# 20190105_ORIGAMI_V1-1-V-FIXED.net
KiCad netlist of a schematic drawn in EAGLE
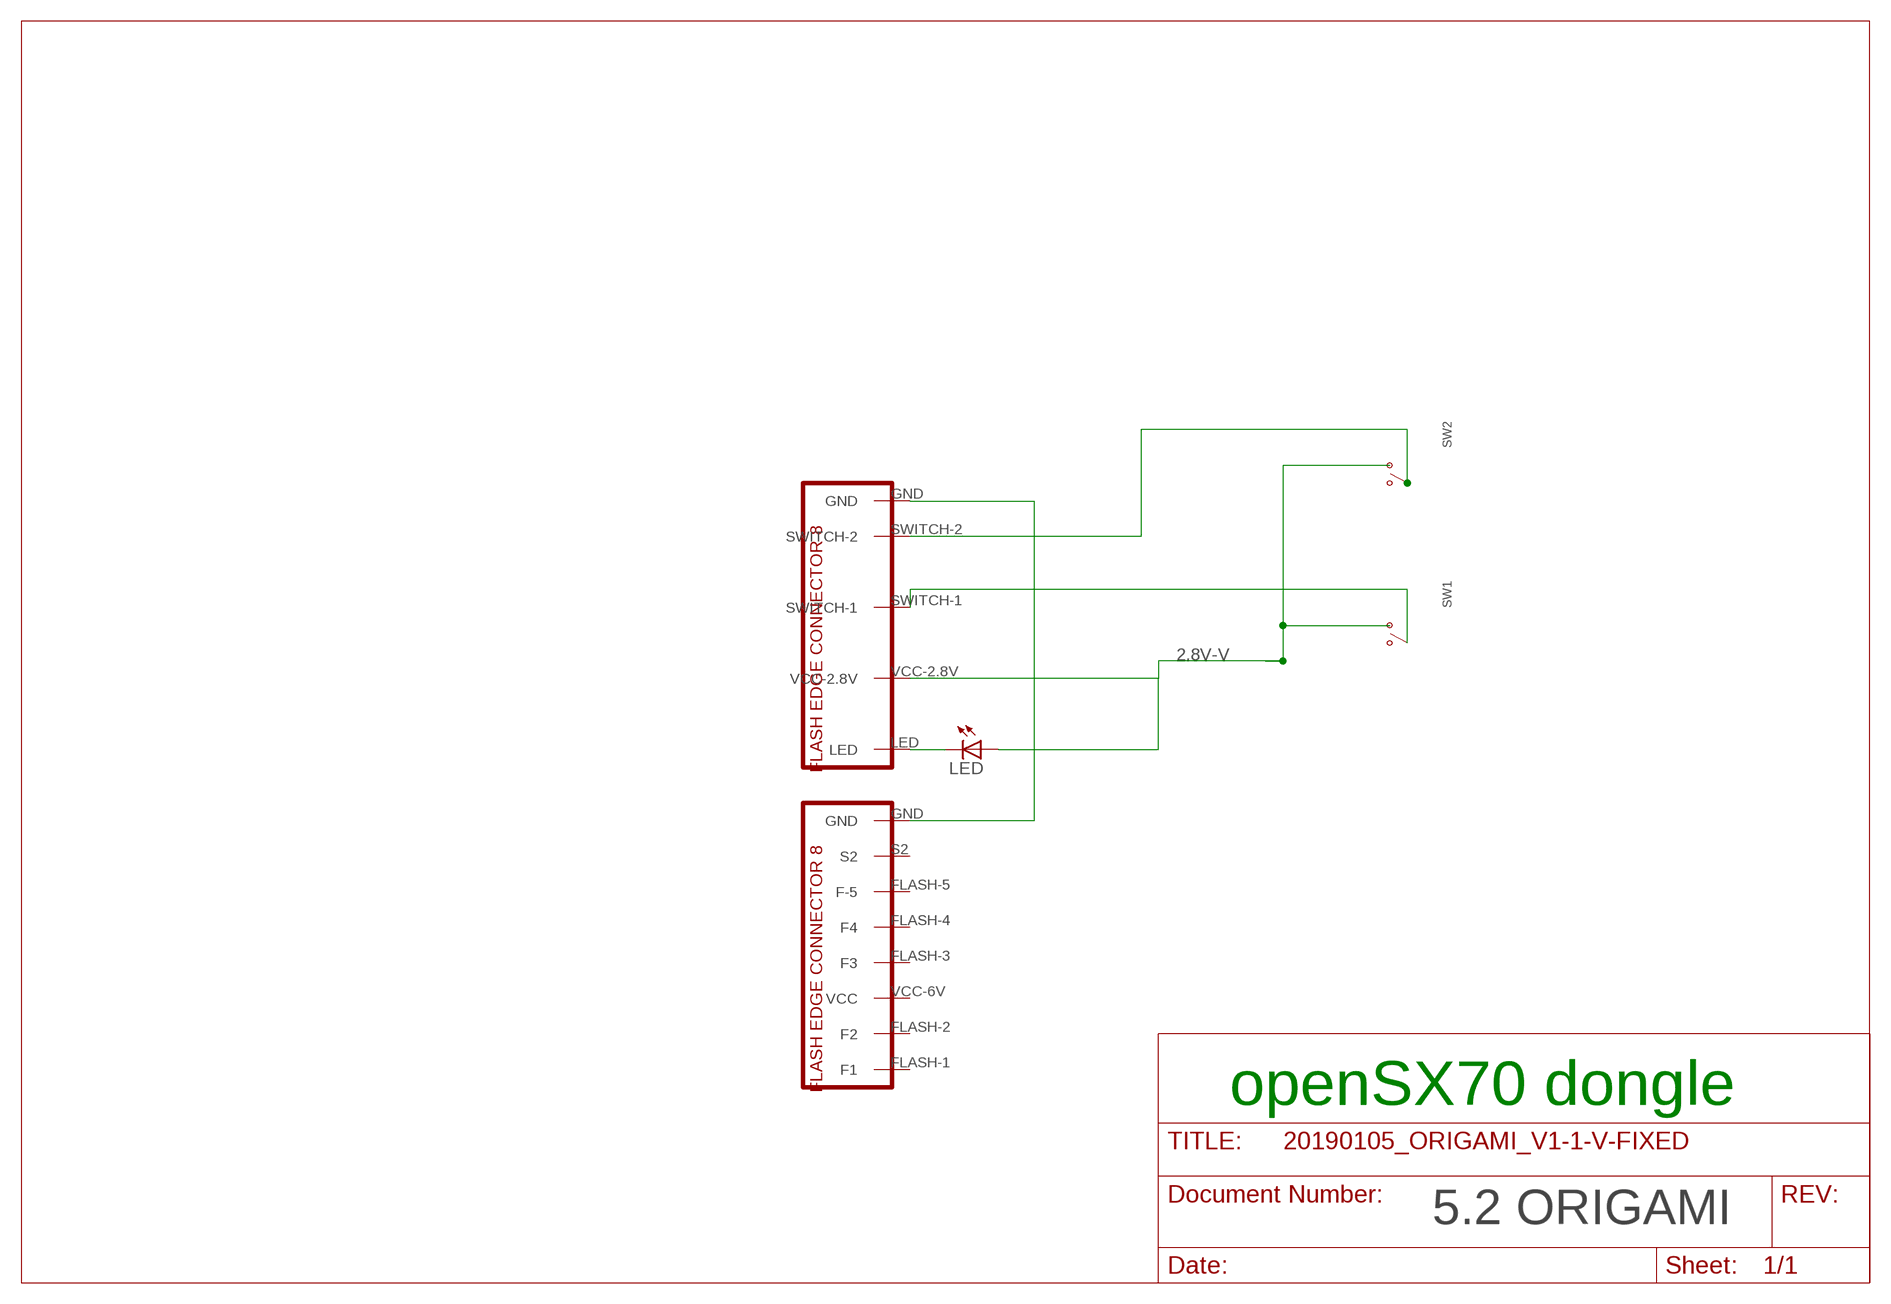
[diagram p0: schematic, sheet 1]

(export (version "E")
  (design (tool "Eeschema 10.0.6"))
  (components
    (comp (ref "LED")
      (value "LEDCHIP-LED0805")
      (footprint "eagle-import:CHIP-LED0805")
      (libsource (lib "eagle-import") (part "LEDCHIP-LED0805"))
    )
    (comp (ref "SW1")
      (value "MK-12C02 G1.5")
      (footprint "eagle-import:SSSS810701")
      (fields (field (name "MF") "ALPS") (field (name "MP") "SSSS810701"))
      (libsource (lib "eagle-import") (part "SSSS810701"))
    )
    (comp (ref "SW2")
      (value "MK-12C02 G1.5")
      (footprint "eagle-import:SSSS810701")
      (fields (field (name "MF") "ALPS") (field (name "MP") "SSSS810701"))
      (libsource (lib "eagle-import") (part "SSSS810701"))
    )
    (comp (ref "U$1")
      (value "FLASH-BRIDGE-SW1-SW2-LED-SMALL")
      (footprint "eagle-import:FLASH-8-BRIDGE-SW1-SW2-LED-SMALL")
      (libsource (lib "eagle-import") (part "FLASH-BRIDGE-SW1-SW2-LED-SMALL"))
    )
    (comp (ref "U$2")
      (value "SX70-FLASH-EDGE8-MALE-LONG")
      (footprint "eagle-import:SX70-FLASH-EDGE8-2")
      (libsource (lib "eagle-import") (part "SX70-FLASH-EDGE8-MALE-LONG"))
    )
  )
  (nets
    (net (code "1") (name "/2.8V-V") (class "Default")
      (node (ref "LED") (pin "A") (pinfunction "A_A") (pintype "passive"))
      (node (ref "SW1") (pin "1") (pinfunction "B_1") (pintype "bidirectional"))
      (node (ref "SW2") (pin "1") (pinfunction "B_1") (pintype "bidirectional"))
      (node (ref "U$1") (pin "VCC-2.8V") (pinfunction "VCC-2.8V_VCC-2.8V") (pintype "bidirectional"))
    )
    (net (code "2") (name "Net-(LED-PadC)") (class "Default")
      (node (ref "LED") (pin "C") (pinfunction "C_C") (pintype "passive"))
      (node (ref "U$1") (pin "LED") (pinfunction "LED_LED") (pintype "bidirectional"))
    )
    (net (code "3") (name "Net-(SW1-COM)") (class "Default")
      (node (ref "SW1") (pin "2") (pinfunction "COM_2") (pintype "bidirectional"))
      (node (ref "U$1") (pin "SWITCH-1") (pinfunction "SWITCH-1_SWITCH-1") (pintype "bidirectional"))
    )
    (net (code "4") (name "Net-(SW2-COM)") (class "Default")
      (node (ref "SW2") (pin "2") (pinfunction "COM_2") (pintype "bidirectional"))
      (node (ref "U$1") (pin "SWITCH-2") (pinfunction "SWITCH-2_SWITCH-2") (pintype "bidirectional"))
    )
    (net (code "5") (name "Net-(U$1-PadGND)") (class "Default")
      (node (ref "U$1") (pin "GND") (pinfunction "GND_GND") (pintype "bidirectional"))
      (node (ref "U$2") (pin "GND") (pinfunction "GND_GND") (pintype "bidirectional"))
    )
    (net (code "6") (name "unconnected-(SW1-A-Pad3)") (class "Default")
      (node (ref "SW1") (pin "3") (pinfunction "A_3") (pintype "bidirectional"))
    )
    (net (code "7") (name "unconnected-(SW2-A-Pad3)") (class "Default")
      (node (ref "SW2") (pin "3") (pinfunction "A_3") (pintype "bidirectional"))
    )
    (net (code "8") (name "unconnected-(U$2-F-5-PadFLASH-5)") (class "Default")
      (node (ref "U$2") (pin "FLASH-5") (pinfunction "F-5_FLASH-5") (pintype "bidirectional"))
    )
    (net (code "9") (name "unconnected-(U$2-F1-PadFLASH-1)") (class "Default")
      (node (ref "U$2") (pin "FLASH-1") (pinfunction "F1_FLASH-1") (pintype "bidirectional"))
    )
    (net (code "10") (name "unconnected-(U$2-F2-PadFLASH-2)") (class "Default")
      (node (ref "U$2") (pin "FLASH-2") (pinfunction "F2_FLASH-2") (pintype "bidirectional"))
    )
    (net (code "11") (name "unconnected-(U$2-F3-PadFLASH-3)") (class "Default")
      (node (ref "U$2") (pin "FLASH-3") (pinfunction "F3_FLASH-3") (pintype "bidirectional"))
    )
    (net (code "12") (name "unconnected-(U$2-F4-PadFLASH-4)") (class "Default")
      (node (ref "U$2") (pin "FLASH-4") (pinfunction "F4_FLASH-4") (pintype "bidirectional"))
    )
    (net (code "13") (name "unconnected-(U$2-PadS2)") (class "Default")
      (node (ref "U$2") (pin "S2") (pinfunction "S2_S2") (pintype "bidirectional"))
    )
    (net (code "14") (name "unconnected-(U$2-VCC-PadVCC-6V)") (class "Default")
      (node (ref "U$2") (pin "VCC-6V") (pinfunction "VCC_VCC-6V") (pintype "bidirectional"))
    )
  )
)
